# Gyroscope.net
KiCad netlist of a schematic drawn in Altium Designer
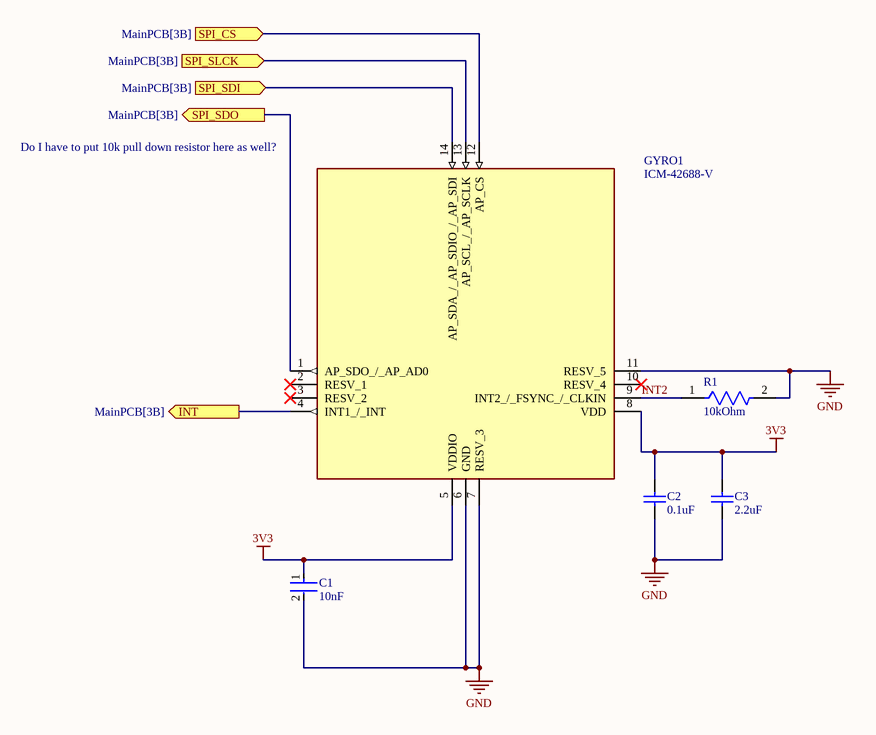
[diagram p0: Gyroscope.SchDoc]

(export (version "E")
  (design (tool "Eeschema 10.0.6"))
  (components
    (comp (ref "C1")
      (value "10nF")
      (footprint "FP-0402-L_1_0_1-W_0_5_0_1-IPC_C")
      (description "04023C103KAT2A")
      (fields (field (name "TOLERANCE") "10%") (field (name "VOLTAGE") "25V"))
      (libsource (lib "Altium Content Vault") (part "b4654b650e69147ec39a6b967a45e02"))
    )
    (comp (ref "C2")
      (value "0.1uF")
      (footprint "CAPC1005X56X25LL10T15")
      (description "04023C104JAT2A")
      (fields (field (name "MANUFACTURER") "AVX Interconnect / Elco"))
      (libsource (lib "Altium Content Vault") (part "CAP"))
    )
    (comp (ref "C3")
      (value "2.2uF")
      (footprint "CAPC0603(1608)100_L")
      (description "C0603C225K8PAC")
      (fields (field (name "TOLERANCE") "Â±10%"))
      (libsource (lib "Altium Content Vault") (part "CAP"))
    )
    (comp (ref "GYRO1")
      (value "ICM-42688-V")
      (footprint "SamacSys:IIM42352")
      (description "Accelerometer")
      (fields (field (name "MOUSER PART NUMBER") "410-ICM-42688-V"))
      (libsource (lib "*") (part "ICM-42688-V"))
    )
    (comp (ref "R1")
      (value "10kOhm")
      (footprint "FP-RT0402-MFG")
      (description "RT0402FRE0710KL")
      (fields
        (field (name "MANUFACTURER") "Yageo")
        (field (name "OCTOPART") "https://octopart.com/rt0402fre0710kl-yageo-1293756")
      )
      (libsource (lib "Altium Content Vault") (part "1029c3af85768c4190bb7ad29bc67b5"))
    )
  )
  (nets
    (net (code "1") (name "/INT") (class "Default")
      (node (ref "GYRO1") (pin "4") (pinfunction "INT1_/_INT_4") (pintype "output"))
    )
    (net (code "2") (name "/INT2") (class "Default")
      (node (ref "GYRO1") (pin "9") (pinfunction "INT2_/_FSYNC_/_CLKIN_9") (pintype "passive"))
      (node (ref "R1") (pin "1") (pinfunction "1_1") (pintype "passive"))
    )
    (net (code "3") (name "/SPI_CS") (class "Default")
      (node (ref "GYRO1") (pin "12") (pinfunction "AP_CS_12") (pintype "input"))
    )
    (net (code "4") (name "/SPI_SDI") (class "Default")
      (node (ref "GYRO1") (pin "14") (pinfunction "AP_SDA_/_AP_SDIO_/_AP_SDI_14") (pintype "input"))
    )
    (net (code "5") (name "/SPI_SDO") (class "Default")
      (node (ref "GYRO1") (pin "1") (pinfunction "AP_SDO_/_AP_AD0_1") (pintype "output"))
    )
    (net (code "6") (name "/SPI_SLCK") (class "Default")
      (node (ref "GYRO1") (pin "13") (pinfunction "AP_SCL_/_AP_SCLK_13") (pintype "input"))
    )
    (net (code "7") (name "3V3") (class "Default")
      (node (ref "C1") (pin "1") (pinfunction "1_1") (pintype "passive"))
      (node (ref "C2") (pin "2") (pinfunction "2_2") (pintype "passive"))
      (node (ref "C3") (pin "1") (pinfunction "1_1") (pintype "passive"))
      (node (ref "GYRO1") (pin "5") (pinfunction "VDDIO_5") (pintype "power_in"))
      (node (ref "GYRO1") (pin "8") (pinfunction "VDD_8") (pintype "power_in"))
    )
    (net (code "8") (name "GND") (class "Default")
      (node (ref "C1") (pin "2") (pinfunction "2_2") (pintype "passive"))
      (node (ref "C2") (pin "1") (pinfunction "1_1") (pintype "passive"))
      (node (ref "C3") (pin "2") (pinfunction "2_2") (pintype "passive"))
      (node (ref "GYRO1") (pin "11") (pinfunction "RESV_5_11") (pintype "passive"))
      (node (ref "GYRO1") (pin "6") (pinfunction "GND_6") (pintype "power_in"))
      (node (ref "GYRO1") (pin "7") (pinfunction "RESV_3_7") (pintype "passive"))
      (node (ref "R1") (pin "2") (pinfunction "2_2") (pintype "passive"))
    )
    (net (code "9") (name "unconnected-(GYRO1-RESV_1-Pad2)") (class "Default")
      (node (ref "GYRO1") (pin "2") (pinfunction "RESV_1_2") (pintype "passive+no_connect"))
    )
    (net (code "10") (name "unconnected-(GYRO1-RESV_2-Pad3)") (class "Default")
      (node (ref "GYRO1") (pin "3") (pinfunction "RESV_2_3") (pintype "passive+no_connect"))
    )
    (net (code "11") (name "unconnected-(GYRO1-RESV_4-Pad10)") (class "Default")
      (node (ref "GYRO1") (pin "10") (pinfunction "RESV_4_10") (pintype "passive+no_connect"))
    )
  )
)
